# hx_esp32c5_cam_proto.net
KiCad netlist of a schematic drawn in EasyEDA Pro
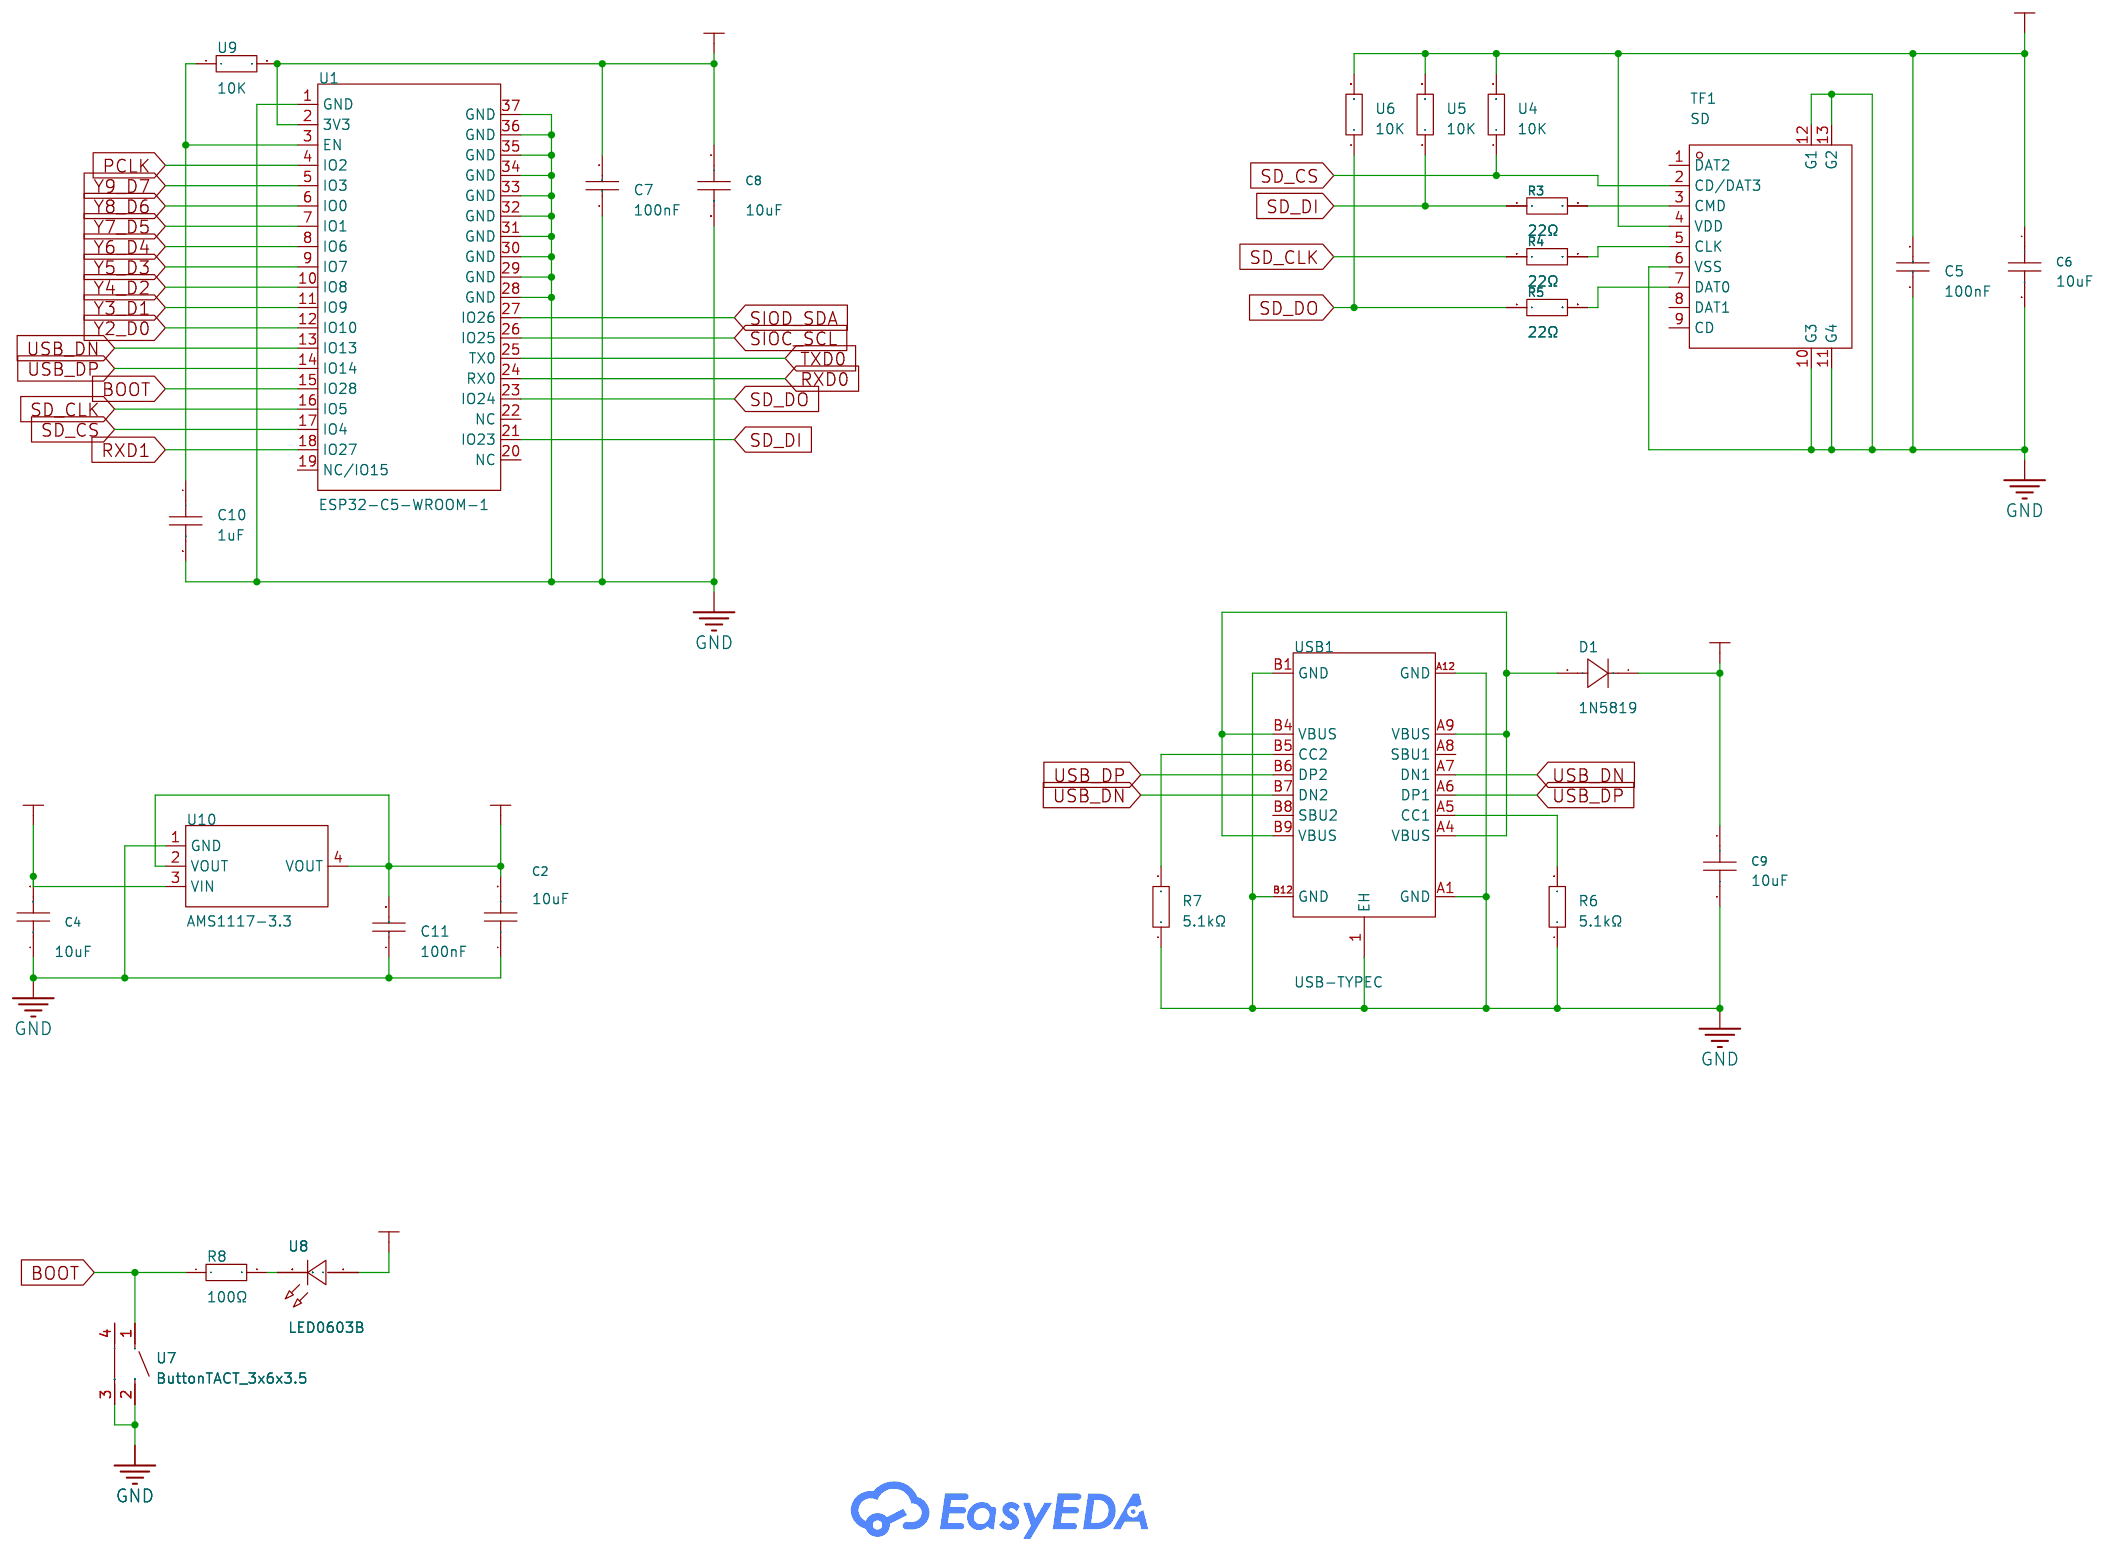
[diagram p0: schematic sheet]

(export (version "E")
  (design (tool "Eeschema 10.0.6"))
  (components
    (comp (ref "C2")
      (value "10uF")
      (footprint "easyedapro:C0603")
      (fields (field (name "Manufacturer") "SAMSUNG(三星)"))
      (libsource (lib "easyedapro") (part "10UF"))
    )
    (comp (ref "C4")
      (value "10uF")
      (footprint "easyedapro:C0603")
      (fields (field (name "Manufacturer") "SAMSUNG(三星)"))
      (libsource (lib "easyedapro") (part "10UF"))
    )
    (comp (ref "C5")
      (value "100nF")
      (footprint "easyedapro:C0805")
      (description "Capacitance:100nF Tolerance:±10% Tolerance:±10% Voltage Rating:100V Temperature Coefficient:X7R")
      (fields
        (field (name "Manufacturer Part") "CL21B104KCFNNNE")
        (field (name "Manufacturer") "SAMSUNG(三星)")
      )
      (libsource (lib "easyedapro") (part "CL21B104KCFNNNE"))
    )
    (comp (ref "C6")
      (value "10uF")
      (footprint "easyedapro:C0603")
      (fields (field (name "Manufacturer") "SAMSUNG(三星)"))
      (libsource (lib "easyedapro") (part "10UF"))
    )
    (comp (ref "C7")
      (value "100nF")
      (footprint "easyedapro:C0805")
      (description "Capacitance:100nF Tolerance:±10% Tolerance:±10% Voltage Rating:100V Temperature Coefficient:X7R")
      (fields
        (field (name "Manufacturer Part") "CL21B104KCFNNNE")
        (field (name "Manufacturer") "SAMSUNG(三星)")
      )
      (libsource (lib "easyedapro") (part "CL21B104KCFNNNE"))
    )
    (comp (ref "C8")
      (value "10uF")
      (footprint "easyedapro:C0603")
      (fields (field (name "Manufacturer") "SAMSUNG(三星)"))
      (libsource (lib "easyedapro") (part "10UF"))
    )
    (comp (ref "C9")
      (value "10uF")
      (footprint "easyedapro:C0603")
      (fields (field (name "Manufacturer") "SAMSUNG(三星)"))
      (libsource (lib "easyedapro") (part "10UF"))
    )
    (comp (ref "C10")
      (value "1uF")
      (footprint "easyedapro:C0603")
      (fields (field (name "Manufacturer Part") "CGB3B1X6S1C105K055AC") (field (name "Manufacturer") "TDK"))
      (libsource (lib "easyedapro") (part "CGB3B1X6S1C105K055AC"))
    )
    (comp (ref "C11")
      (value "100nF")
      (footprint "easyedapro:C0805")
      (description "Capacitance:100nF Tolerance:±10% Tolerance:±10% Voltage Rating:100V Temperature Coefficient:X7R")
      (fields
        (field (name "Manufacturer Part") "CL21B104KCFNNNE")
        (field (name "Manufacturer") "SAMSUNG(三星)")
      )
      (libsource (lib "easyedapro") (part "CL21B104KCFNNNE"))
    )
    (comp (ref "D1")
      (value "1N5819")
      (footprint "easyedapro:SMA_L4.3-W2.7-LS5.1-RD")
      (libsource (lib "easyedapro") (part "1N5819_C2892330"))
    )
    (comp (ref "R3")
      (value "22Ω")
      (footprint "easyedapro:R0805")
      (fields (field (name "Manufacturer Part") "RMC0805225%N") (field (name "Manufacturer") "Tyohm(幸亚电阻)"))
      (libsource (lib "easyedapro") (part "RMC0805225%N"))
    )
    (comp (ref "R4")
      (value "22Ω")
      (footprint "easyedapro:R0805")
      (fields (field (name "Manufacturer Part") "RMC0805225%N") (field (name "Manufacturer") "Tyohm(幸亚电阻)"))
      (libsource (lib "easyedapro") (part "RMC0805225%N"))
    )
    (comp (ref "R5")
      (value "22Ω")
      (footprint "easyedapro:R0805")
      (fields (field (name "Manufacturer Part") "RMC0805225%N") (field (name "Manufacturer") "Tyohm(幸亚电阻)"))
      (libsource (lib "easyedapro") (part "RMC0805225%N"))
    )
    (comp (ref "R6")
      (value "5.1kΩ")
      (footprint "easyedapro:R0805")
      (fields (field (name "Manufacturer Part") "AECR0805F5K10K9") (field (name "Manufacturer") "RESI(开步睿思)"))
      (libsource (lib "easyedapro") (part "AECR0805F5K10K9"))
    )
    (comp (ref "R7")
      (value "5.1kΩ")
      (footprint "easyedapro:R0805")
      (fields (field (name "Manufacturer Part") "AECR0805F5K10K9") (field (name "Manufacturer") "RESI(开步睿思)"))
      (libsource (lib "easyedapro") (part "AECR0805F5K10K9"))
    )
    (comp (ref "R8")
      (value "100Ω")
      (footprint "easyedapro:R0805")
      (fields (field (name "Manufacturer Part") "MCR10EZHJ101") (field (name "Manufacturer") "ROHM(罗姆)"))
      (libsource (lib "easyedapro") (part "MCR10EZHJ101"))
    )
    (comp (ref "TF1")
      (value "SD")
      (footprint "easyedapro:TF-SMD_TF-15-15")
      (libsource (lib "easyedapro") (part "SD"))
    )
    (comp (ref "U1")
      (value "ESP32-C5-WROOM-1")
      (footprint "easyedapro:COMM-SMD_37P-P1.27-L27.5-W18.0-ESP32-C5-WROOM-1")
      (libsource (lib "easyedapro") (part "ESP32-C5-WROOM-1"))
    )
    (comp (ref "U4") (value "10K") (footprint "easyedapro:R0805") (libsource (lib "easyedapro") (part "10K")))
    (comp (ref "U5") (value "10K") (footprint "easyedapro:R0805") (libsource (lib "easyedapro") (part "10K")))
    (comp (ref "U6") (value "10K") (footprint "easyedapro:R0805") (libsource (lib "easyedapro") (part "10K")))
    (comp (ref "U7")
      (value "ButtonTACT_3x6x3.5")
      (footprint "easyedapro:SW-SMD_L7.8-W3.5-P4.00-EH")
      (libsource (lib "easyedapro") (part "BUTTONTACT_3X6X3.5"))
    )
    (comp (ref "U8")
      (value "LED0603B")
      (footprint "easyedapro:LED0603-R-RD_BLUE")
      (libsource (lib "easyedapro") (part "LED0603B_C9900038277"))
    )
    (comp (ref "U9") (value "10K") (footprint "easyedapro:R0805") (libsource (lib "easyedapro") (part "10K")))
    (comp (ref "U10")
      (value "AMS1117-3.3")
      (footprint "easyedapro:SOT-223-3_L6.5-W3.4-P2.30-LS7.0-BR")
      (fields (field (name "Manufacturer") "AMS"))
      (libsource (lib "easyedapro") (part "AMS1117-3.3"))
    )
    (comp (ref "USB1")
      (value "USB-TYPEC")
      (footprint "easyedapro:TYPE-C-SMD_16P-EH4")
      (libsource (lib "easyedapro") (part "USB-TYPEC"))
    )
  )
  (nets
    (net (code "1") (name "BOOT") (class "Default")
      (node (ref "R8") (pin "1") (pinfunction "1_1") (pintype "unspecified"))
      (node (ref "U1") (pin "15") (pinfunction "IO28_15") (pintype "unspecified"))
      (node (ref "U7") (pin "1") (pinfunction "1_1") (pintype "unspecified"))
    )
    (net (code "2") (name "GND") (class "Default")
      (node (ref "C10") (pin "2") (pinfunction "2_2") (pintype "unspecified"))
      (node (ref "C11") (pin "1") (pinfunction "1_1") (pintype "input"))
      (node (ref "C2") (pin "1") (pinfunction "1_1") (pintype "input"))
      (node (ref "C4") (pin "1") (pinfunction "1_1") (pintype "input"))
      (node (ref "C5") (pin "1") (pinfunction "1_1") (pintype "input"))
      (node (ref "C6") (pin "2") (pinfunction "2_2") (pintype "input"))
      (node (ref "C7") (pin "1") (pinfunction "1_1") (pintype "input"))
      (node (ref "C8") (pin "2") (pinfunction "2_2") (pintype "input"))
      (node (ref "C9") (pin "2") (pinfunction "2_2") (pintype "input"))
      (node (ref "R6") (pin "1") (pinfunction "1_1") (pintype "unspecified"))
      (node (ref "R7") (pin "1") (pinfunction "1_1") (pintype "unspecified"))
      (node (ref "TF1") (pin "10") (pinfunction "G3_10") (pintype "unspecified"))
      (node (ref "TF1") (pin "11") (pinfunction "G4_11") (pintype "unspecified"))
      (node (ref "TF1") (pin "12") (pinfunction "G1_12") (pintype "unspecified"))
      (node (ref "TF1") (pin "13") (pinfunction "G2_13") (pintype "unspecified"))
      (node (ref "TF1") (pin "6") (pinfunction "VSS_6") (pintype "unspecified"))
      (node (ref "U1") (pin "1") (pinfunction "GND_1") (pintype "unspecified"))
      (node (ref "U1") (pin "28") (pinfunction "GND_28") (pintype "unspecified"))
      (node (ref "U1") (pin "29") (pinfunction "GND_29") (pintype "unspecified"))
      (node (ref "U1") (pin "30") (pinfunction "GND_30") (pintype "unspecified"))
      (node (ref "U1") (pin "31") (pinfunction "GND_31") (pintype "unspecified"))
      (node (ref "U1") (pin "32") (pinfunction "GND_32") (pintype "unspecified"))
      (node (ref "U1") (pin "33") (pinfunction "GND_33") (pintype "unspecified"))
      (node (ref "U1") (pin "34") (pinfunction "GND_34") (pintype "unspecified"))
      (node (ref "U1") (pin "35") (pinfunction "GND_35") (pintype "unspecified"))
      (node (ref "U1") (pin "36") (pinfunction "GND_36") (pintype "unspecified"))
      (node (ref "U1") (pin "37") (pinfunction "GND_37") (pintype "unspecified"))
      (node (ref "U10") (pin "1") (pinfunction "GND_1") (pintype "unspecified"))
      (node (ref "U7") (pin "2") (pinfunction "2_2") (pintype "unspecified"))
      (node (ref "U7") (pin "3") (pinfunction "3_3") (pintype "unspecified"))
      (node (ref "USB1") (pin "1") (pinfunction "EH_1") (pintype "unspecified"))
      (node (ref "USB1") (pin "A1") (pinfunction "GND_A1") (pintype "unspecified"))
      (node (ref "USB1") (pin "A12") (pinfunction "GND_A12") (pintype "unspecified"))
      (node (ref "USB1") (pin "B1") (pinfunction "GND_B1") (pintype "unspecified"))
      (node (ref "USB1") (pin "B12") (pinfunction "GND_B12") (pintype "unspecified"))
    )
    (net (code "3") (name "Net-(D1-A)") (class "Default")
      (node (ref "D1") (pin "2") (pinfunction "A_2") (pintype "input"))
      (node (ref "USB1") (pin "A4") (pinfunction "VBUS_A4") (pintype "unspecified"))
      (node (ref "USB1") (pin "A9") (pinfunction "VBUS_A9") (pintype "unspecified"))
      (node (ref "USB1") (pin "B4") (pinfunction "VBUS_B4") (pintype "unspecified"))
      (node (ref "USB1") (pin "B9") (pinfunction "VBUS_B9") (pintype "unspecified"))
    )
    (net (code "4") (name "Net-(TF1-CLK)") (class "Default")
      (node (ref "R4") (pin "2") (pinfunction "2_2") (pintype "input"))
      (node (ref "TF1") (pin "5") (pinfunction "CLK_5") (pintype "unspecified"))
    )
    (net (code "5") (name "Net-(TF1-CMD)") (class "Default")
      (node (ref "R3") (pin "2") (pinfunction "2_2") (pintype "input"))
      (node (ref "TF1") (pin "3") (pinfunction "CMD_3") (pintype "unspecified"))
    )
    (net (code "6") (name "Net-(TF1-DAT0)") (class "Default")
      (node (ref "R5") (pin "2") (pinfunction "2_2") (pintype "input"))
      (node (ref "TF1") (pin "7") (pinfunction "DAT0_7") (pintype "unspecified"))
    )
    (net (code "7") (name "Net-(U1-EN)") (class "Default")
      (node (ref "C10") (pin "1") (pinfunction "1_1") (pintype "unspecified"))
      (node (ref "U1") (pin "3") (pinfunction "EN_3") (pintype "unspecified"))
      (node (ref "U9") (pin "1") (pinfunction "1_1") (pintype "unspecified"))
    )
    (net (code "8") (name "Net-(U8-C)") (class "Default")
      (node (ref "R8") (pin "2") (pinfunction "2_2") (pintype "unspecified"))
      (node (ref "U8") (pin "2") (pinfunction "C_2") (pintype "unspecified"))
    )
    (net (code "9") (name "Net-(USB1-CC1)") (class "Default")
      (node (ref "R6") (pin "2") (pinfunction "2_2") (pintype "unspecified"))
      (node (ref "USB1") (pin "A5") (pinfunction "CC1_A5") (pintype "unspecified"))
    )
    (net (code "10") (name "Net-(USB1-CC2)") (class "Default")
      (node (ref "R7") (pin "2") (pinfunction "2_2") (pintype "unspecified"))
      (node (ref "USB1") (pin "B5") (pinfunction "CC2_B5") (pintype "unspecified"))
    )
    (net (code "11") (name "PCLK") (class "Default")
      (node (ref "U1") (pin "4") (pinfunction "IO2_4") (pintype "unspecified"))
    )
    (net (code "12") (name "RXD0") (class "Default")
      (node (ref "U1") (pin "24") (pinfunction "RX0_24") (pintype "unspecified"))
    )
    (net (code "13") (name "RXD1") (class "Default")
      (node (ref "U1") (pin "18") (pinfunction "IO27_18") (pintype "unspecified"))
    )
    (net (code "14") (name "SD_CLK") (class "Default")
      (node (ref "R4") (pin "1") (pinfunction "1_1") (pintype "input"))
      (node (ref "U1") (pin "16") (pinfunction "IO5_16") (pintype "unspecified"))
    )
    (net (code "15") (name "SD_CS") (class "Default")
      (node (ref "TF1") (pin "2") (pinfunction "CD/DAT3_2") (pintype "unspecified"))
      (node (ref "U1") (pin "17") (pinfunction "IO4_17") (pintype "unspecified"))
      (node (ref "U4") (pin "1") (pinfunction "1_1") (pintype "unspecified"))
    )
    (net (code "16") (name "SD_DI") (class "Default")
      (node (ref "R3") (pin "1") (pinfunction "1_1") (pintype "input"))
      (node (ref "U1") (pin "21") (pinfunction "IO23_21") (pintype "unspecified"))
      (node (ref "U5") (pin "1") (pinfunction "1_1") (pintype "unspecified"))
    )
    (net (code "17") (name "SD_DO") (class "Default")
      (node (ref "R5") (pin "1") (pinfunction "1_1") (pintype "input"))
      (node (ref "U1") (pin "23") (pinfunction "IO24_23") (pintype "unspecified"))
      (node (ref "U6") (pin "1") (pinfunction "1_1") (pintype "unspecified"))
    )
    (net (code "18") (name "SIOC_SCL") (class "Default")
      (node (ref "U1") (pin "26") (pinfunction "IO25_26") (pintype "unspecified"))
    )
    (net (code "19") (name "SIOD_SDA") (class "Default")
      (node (ref "U1") (pin "27") (pinfunction "IO26_27") (pintype "unspecified"))
    )
    (net (code "20") (name "TXD0") (class "Default")
      (node (ref "U1") (pin "25") (pinfunction "TX0_25") (pintype "unspecified"))
    )
    (net (code "21") (name "USB_DN") (class "Default")
      (node (ref "U1") (pin "13") (pinfunction "IO13_13") (pintype "unspecified"))
      (node (ref "USB1") (pin "A7") (pinfunction "DN1_A7") (pintype "unspecified"))
      (node (ref "USB1") (pin "B7") (pinfunction "DN2_B7") (pintype "unspecified"))
    )
    (net (code "22") (name "USB_DP") (class "Default")
      (node (ref "U1") (pin "14") (pinfunction "IO14_14") (pintype "unspecified"))
      (node (ref "USB1") (pin "A6") (pinfunction "DP1_A6") (pintype "unspecified"))
      (node (ref "USB1") (pin "B6") (pinfunction "DP2_B6") (pintype "unspecified"))
    )
    (net (code "23") (name "VCC_3.3V") (class "Default")
      (node (ref "C11") (pin "2") (pinfunction "2_2") (pintype "input"))
      (node (ref "C2") (pin "2") (pinfunction "2_2") (pintype "input"))
      (node (ref "C5") (pin "2") (pinfunction "2_2") (pintype "input"))
      (node (ref "C6") (pin "1") (pinfunction "1_1") (pintype "input"))
      (node (ref "C7") (pin "2") (pinfunction "2_2") (pintype "input"))
      (node (ref "C8") (pin "1") (pinfunction "1_1") (pintype "input"))
      (node (ref "TF1") (pin "4") (pinfunction "VDD_4") (pintype "unspecified"))
      (node (ref "U1") (pin "2") (pinfunction "3V3_2") (pintype "unspecified"))
      (node (ref "U10") (pin "2") (pinfunction "VOUT_2") (pintype "unspecified"))
      (node (ref "U10") (pin "4") (pinfunction "VOUT_4") (pintype "unspecified"))
      (node (ref "U4") (pin "2") (pinfunction "2_2") (pintype "unspecified"))
      (node (ref "U5") (pin "2") (pinfunction "2_2") (pintype "unspecified"))
      (node (ref "U6") (pin "2") (pinfunction "2_2") (pintype "unspecified"))
      (node (ref "U8") (pin "1") (pinfunction "A_1") (pintype "unspecified"))
      (node (ref "U9") (pin "2") (pinfunction "2_2") (pintype "unspecified"))
    )
    (net (code "24") (name "VCC_5V") (class "Default")
      (node (ref "C4") (pin "2") (pinfunction "2_2") (pintype "input"))
      (node (ref "C9") (pin "1") (pinfunction "1_1") (pintype "input"))
      (node (ref "D1") (pin "1") (pinfunction "K_1") (pintype "input"))
      (node (ref "U10") (pin "3") (pinfunction "VIN_3") (pintype "unspecified"))
    )
    (net (code "25") (name "Y2_D0") (class "Default")
      (node (ref "U1") (pin "12") (pinfunction "IO10_12") (pintype "unspecified"))
    )
    (net (code "26") (name "Y3_D1") (class "Default")
      (node (ref "U1") (pin "11") (pinfunction "IO9_11") (pintype "unspecified"))
    )
    (net (code "27") (name "Y4_D2") (class "Default")
      (node (ref "U1") (pin "10") (pinfunction "IO8_10") (pintype "unspecified"))
    )
    (net (code "28") (name "Y5_D3") (class "Default")
      (node (ref "U1") (pin "9") (pinfunction "IO7_9") (pintype "unspecified"))
    )
    (net (code "29") (name "Y6_D4") (class "Default")
      (node (ref "U1") (pin "8") (pinfunction "IO6_8") (pintype "unspecified"))
    )
    (net (code "30") (name "Y7_D5") (class "Default")
      (node (ref "U1") (pin "7") (pinfunction "IO1_7") (pintype "unspecified"))
    )
    (net (code "31") (name "Y8_D6") (class "Default")
      (node (ref "U1") (pin "6") (pinfunction "IO0_6") (pintype "unspecified"))
    )
    (net (code "32") (name "Y9_D7") (class "Default")
      (node (ref "U1") (pin "5") (pinfunction "IO3_5") (pintype "unspecified"))
    )
    (net (code "33") (name "unconnected-(TF1-CD-Pad9)") (class "Default")
      (node (ref "TF1") (pin "9") (pinfunction "CD_9") (pintype "unspecified"))
    )
    (net (code "34") (name "unconnected-(TF1-DAT1-Pad8)") (class "Default")
      (node (ref "TF1") (pin "8") (pinfunction "DAT1_8") (pintype "unspecified"))
    )
    (net (code "35") (name "unconnected-(TF1-DAT2-Pad1)") (class "Default")
      (node (ref "TF1") (pin "1") (pinfunction "DAT2_1") (pintype "unspecified"))
    )
    (net (code "36") (name "unconnected-(U1-NC-Pad20)") (class "Default")
      (node (ref "U1") (pin "20") (pinfunction "NC_20") (pintype "unspecified"))
    )
    (net (code "37") (name "unconnected-(U1-NC-Pad22)") (class "Default")
      (node (ref "U1") (pin "22") (pinfunction "NC_22") (pintype "unspecified"))
    )
    (net (code "38") (name "unconnected-(U1-NC{slash}IO15-Pad19)") (class "Default")
      (node (ref "U1") (pin "19") (pinfunction "NC/IO15_19") (pintype "unspecified"))
    )
    (net (code "39") (name "unconnected-(U7-Pad4)") (class "Default")
      (node (ref "U7") (pin "4") (pinfunction "4_4") (pintype "unspecified"))
    )
    (net (code "40") (name "unconnected-(USB1-SBU1-PadA8)") (class "Default")
      (node (ref "USB1") (pin "A8") (pinfunction "SBU1_A8") (pintype "unspecified"))
    )
    (net (code "41") (name "unconnected-(USB1-SBU2-PadB8)") (class "Default")
      (node (ref "USB1") (pin "B8") (pinfunction "SBU2_B8") (pintype "unspecified"))
    )
  )
)
